# Module_main.net
KiCad netlist of a schematic drawn in Altium Designer
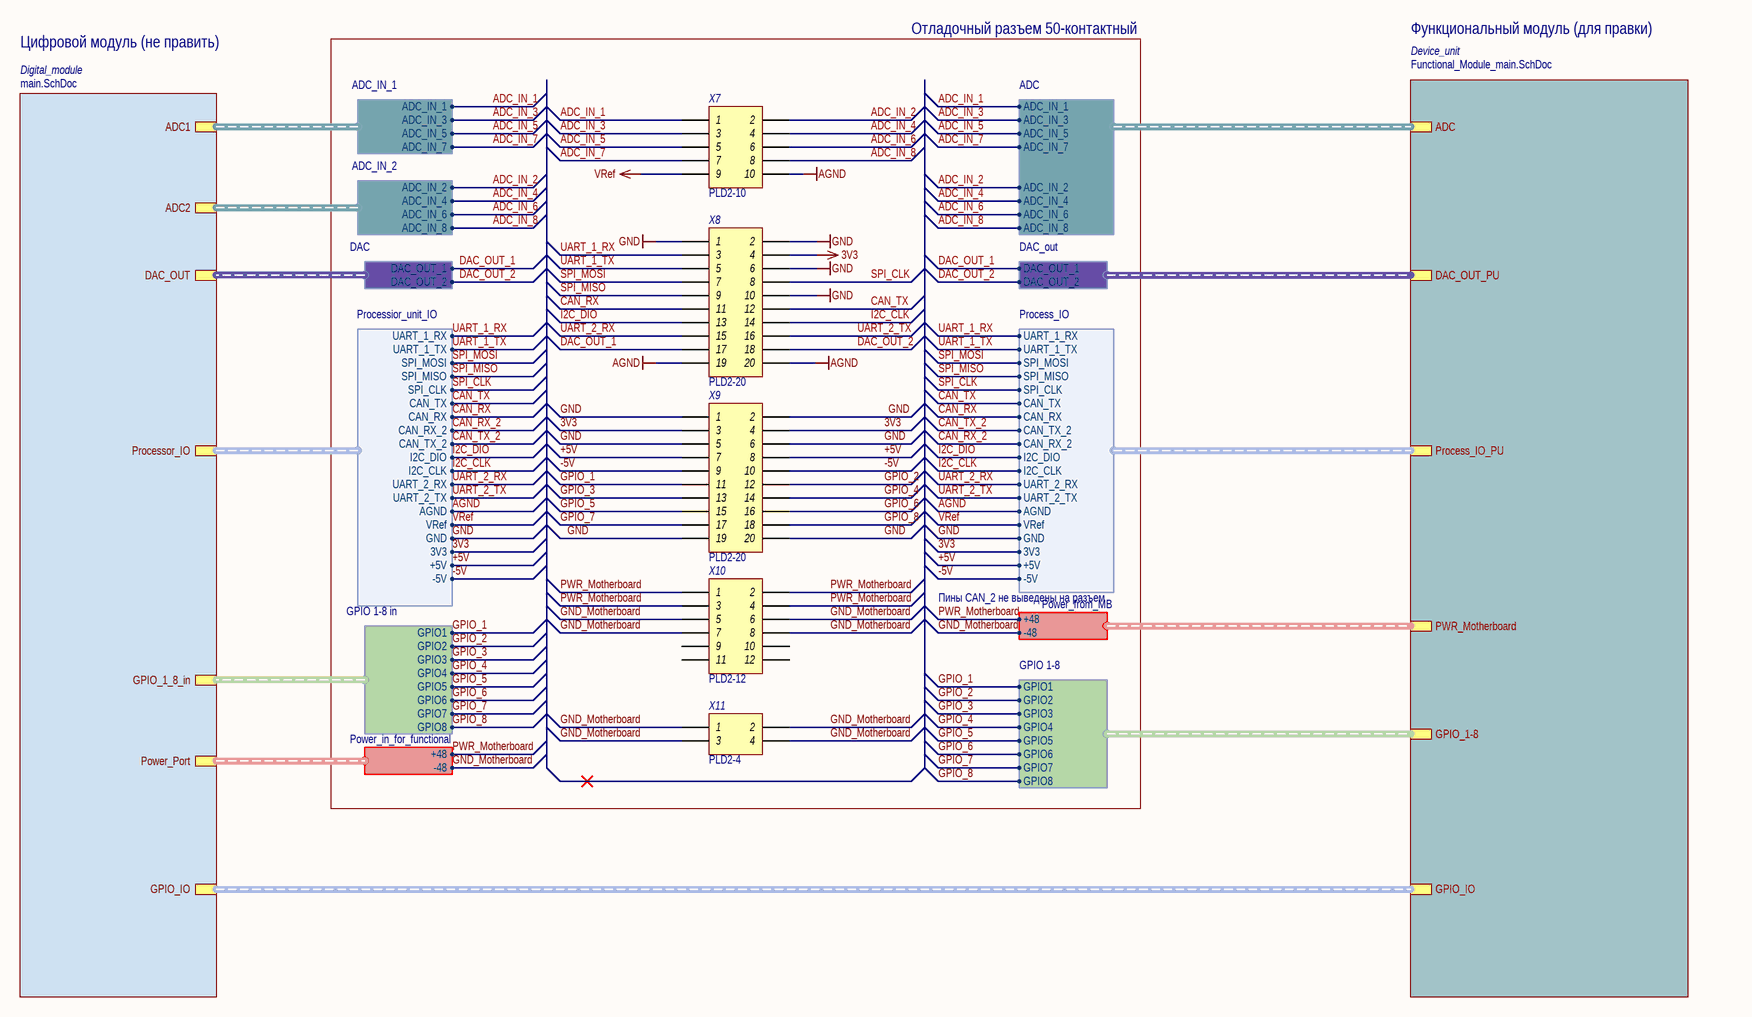
[diagram p0: Module_main.SchDoc]

(export (version "E")
  (design (tool "Eeschema 10.0.6"))
  (components
    (comp (ref "X7")
      (value "Header 2X10")
      (footprint "PBD2-10s")
      (description "Header, 10-Pin, Dual row")
      (fields (field (name "НАИМЕНОВАНИЕ") "PLD2-10"))
      (libsource (lib "Connector") (part "PLD2-10"))
    )
    (comp (ref "X8")
      (value "Header 2X10")
      (footprint "PBD2-20s")
      (description "Header, 12-Pin, Dual row")
      (fields (field (name "НАИМЕНОВАНИЕ") "PLD2-20"))
      (libsource (lib "Connector") (part "PLD2-20"))
    )
    (comp (ref "X9")
      (value "Header 2X10")
      (footprint "PBD2-20s")
      (description "Header, 12-Pin, Dual row")
      (fields (field (name "НАИМЕНОВАНИЕ") "PLD2-20"))
      (libsource (lib "Connector") (part "PLD2-20"))
    )
    (comp (ref "X10")
      (value "Header 2X6")
      (footprint "PLD2-12R 2.54")
      (description "Header, 12-Pin, Dual row")
      (fields (field (name "НАИМЕНОВАНИЕ") "PLD2-12"))
      (libsource (lib "Connector") (part "PLD2-12"))
    )
    (comp (ref "X11")
      (value "Header 2X4")
      (footprint "PLD2-4 R 2.54")
      (description "Header, 4-Pin, Dual row")
      (fields (field (name "НАИМЕНОВАНИЕ") "PLD2-4"))
      (libsource (lib "Connector") (part "PLD2-4"))
    )
  )
  (nets
    (net (code "11") (name "/+5V") (class "Default")
      (node (ref "X9") (pin "7") (pinfunction "7_7") (pintype "passive"))
      (node (ref "X9") (pin "8") (pinfunction "8_8") (pintype "passive"))
    )
    (net (code "12") (name "/-5V") (class "Default")
      (node (ref "X9") (pin "10") (pinfunction "10_10") (pintype "passive"))
      (node (ref "X9") (pin "9") (pinfunction "9_9") (pintype "passive"))
    )
    (net (code "13") (name "/ADC_IN_1") (class "Default")
      (node (ref "X7") (pin "1") (pinfunction "1_1") (pintype "passive"))
    )
    (net (code "14") (name "/ADC_IN_2") (class "Default")
      (node (ref "X7") (pin "2") (pinfunction "2_2") (pintype "passive"))
    )
    (net (code "15") (name "/ADC_IN_3") (class "Default")
      (node (ref "X7") (pin "3") (pinfunction "3_3") (pintype "passive"))
    )
    (net (code "16") (name "/ADC_IN_4") (class "Default")
      (node (ref "X7") (pin "4") (pinfunction "4_4") (pintype "passive"))
    )
    (net (code "17") (name "/ADC_IN_5") (class "Default")
      (node (ref "X7") (pin "5") (pinfunction "5_5") (pintype "passive"))
    )
    (net (code "18") (name "/ADC_IN_6") (class "Default")
      (node (ref "X7") (pin "6") (pinfunction "6_6") (pintype "passive"))
    )
    (net (code "19") (name "/ADC_IN_7") (class "Default")
      (node (ref "X7") (pin "7") (pinfunction "7_7") (pintype "passive"))
    )
    (net (code "20") (name "/ADC_IN_8") (class "Default")
      (node (ref "X7") (pin "8") (pinfunction "8_8") (pintype "passive"))
    )
    (net (code "21") (name "/CAN_RX") (class "Default")
      (node (ref "X8") (pin "11") (pinfunction "11_11") (pintype "passive"))
    )
    (net (code "23") (name "/CAN_TX") (class "Default")
      (node (ref "X8") (pin "12") (pinfunction "12_12") (pintype "passive"))
    )
    (net (code "25") (name "/DAC_OUT_1") (class "Default")
      (node (ref "X8") (pin "17") (pinfunction "17_17") (pintype "passive"))
    )
    (net (code "26") (name "/DAC_OUT_2") (class "Default")
      (node (ref "X8") (pin "18") (pinfunction "18_18") (pintype "passive"))
    )
    (net (code "27") (name "/GND_Motherboard") (class "Default")
      (node (ref "X10") (pin "5") (pinfunction "5_5") (pintype "passive"))
      (node (ref "X10") (pin "6") (pinfunction "6_6") (pintype "passive"))
      (node (ref "X10") (pin "7") (pinfunction "7_7") (pintype "passive"))
      (node (ref "X10") (pin "8") (pinfunction "8_8") (pintype "passive"))
      (node (ref "X11") (pin "1") (pinfunction "1_1") (pintype "passive"))
      (node (ref "X11") (pin "2") (pinfunction "2_2") (pintype "passive"))
      (node (ref "X11") (pin "3") (pinfunction "3_3") (pintype "passive"))
      (node (ref "X11") (pin "4") (pinfunction "4_4") (pintype "passive"))
    )
    (net (code "28") (name "/GPIO_1") (class "Default")
      (node (ref "X9") (pin "11") (pinfunction "11_11") (pintype "passive"))
    )
    (net (code "29") (name "/GPIO_2") (class "Default")
      (node (ref "X9") (pin "12") (pinfunction "12_12") (pintype "passive"))
    )
    (net (code "30") (name "/GPIO_3") (class "Default")
      (node (ref "X9") (pin "13") (pinfunction "13_13") (pintype "passive"))
    )
    (net (code "31") (name "/GPIO_4") (class "Default")
      (node (ref "X9") (pin "14") (pinfunction "14_14") (pintype "passive"))
    )
    (net (code "32") (name "/GPIO_5") (class "Default")
      (node (ref "X9") (pin "15") (pinfunction "15_15") (pintype "passive"))
    )
    (net (code "33") (name "/GPIO_6") (class "Default")
      (node (ref "X9") (pin "16") (pinfunction "16_16") (pintype "passive"))
    )
    (net (code "34") (name "/GPIO_7") (class "Default")
      (node (ref "X9") (pin "17") (pinfunction "17_17") (pintype "passive"))
    )
    (net (code "35") (name "/GPIO_8") (class "Default")
      (node (ref "X9") (pin "18") (pinfunction "18_18") (pintype "passive"))
    )
    (net (code "37") (name "/I2C_CLK") (class "Default")
      (node (ref "X8") (pin "14") (pinfunction "14_14") (pintype "passive"))
    )
    (net (code "38") (name "/I2C_DIO") (class "Default")
      (node (ref "X8") (pin "13") (pinfunction "13_13") (pintype "passive"))
    )
    (net (code "39") (name "/PWR_Motherboard") (class "Default")
      (node (ref "X10") (pin "1") (pinfunction "1_1") (pintype "passive"))
      (node (ref "X10") (pin "2") (pinfunction "2_2") (pintype "passive"))
      (node (ref "X10") (pin "3") (pinfunction "3_3") (pintype "passive"))
      (node (ref "X10") (pin "4") (pinfunction "4_4") (pintype "passive"))
    )
    (net (code "40") (name "/SPI_CLK") (class "Default")
      (node (ref "X8") (pin "8") (pinfunction "8_8") (pintype "passive"))
    )
    (net (code "41") (name "/SPI_MISO") (class "Default")
      (node (ref "X8") (pin "9") (pinfunction "9_9") (pintype "passive"))
    )
    (net (code "42") (name "/SPI_MOSI") (class "Default")
      (node (ref "X8") (pin "7") (pinfunction "7_7") (pintype "passive"))
    )
    (net (code "43") (name "/UART_1_RX") (class "Default")
      (node (ref "X8") (pin "3") (pinfunction "3_3") (pintype "passive"))
    )
    (net (code "44") (name "/UART_1_TX") (class "Default")
      (node (ref "X8") (pin "5") (pinfunction "5_5") (pintype "passive"))
    )
    (net (code "45") (name "/UART_2_RX") (class "Default")
      (node (ref "X8") (pin "15") (pinfunction "15_15") (pintype "passive"))
    )
    (net (code "46") (name "/UART_2_TX") (class "Default")
      (node (ref "X8") (pin "16") (pinfunction "16_16") (pintype "passive"))
    )
    (net (code "58") (name "3V3") (class "Default")
      (node (ref "X8") (pin "4") (pinfunction "4_4") (pintype "passive"))
      (node (ref "X9") (pin "3") (pinfunction "3_3") (pintype "passive"))
      (node (ref "X9") (pin "4") (pinfunction "4_4") (pintype "passive"))
    )
    (net (code "59") (name "AGND") (class "Default")
      (node (ref "X7") (pin "10") (pinfunction "10_10") (pintype "passive"))
      (node (ref "X8") (pin "19") (pinfunction "19_19") (pintype "passive"))
      (node (ref "X8") (pin "20") (pinfunction "20_20") (pintype "passive"))
    )
    (net (code "60") (name "GND") (class "Default")
      (node (ref "X8") (pin "1") (pinfunction "1_1") (pintype "passive"))
      (node (ref "X8") (pin "10") (pinfunction "10_10") (pintype "passive"))
      (node (ref "X8") (pin "2") (pinfunction "2_2") (pintype "passive"))
      (node (ref "X8") (pin "6") (pinfunction "6_6") (pintype "passive"))
      (node (ref "X9") (pin "1") (pinfunction "1_1") (pintype "passive"))
      (node (ref "X9") (pin "19") (pinfunction "19_19") (pintype "passive"))
      (node (ref "X9") (pin "2") (pinfunction "2_2") (pintype "passive"))
      (node (ref "X9") (pin "20") (pinfunction "20_20") (pintype "passive"))
      (node (ref "X9") (pin "5") (pinfunction "5_5") (pintype "passive"))
      (node (ref "X9") (pin "6") (pinfunction "6_6") (pintype "passive"))
    )
    (net (code "61") (name "VRef") (class "Default")
      (node (ref "X7") (pin "9") (pinfunction "9_9") (pintype "passive"))
    )
    (net (code "62") (name "unconnected-(X10-Pad9)") (class "Default")
      (node (ref "X10") (pin "9") (pinfunction "9_9") (pintype "passive"))
    )
    (net (code "63") (name "unconnected-(X10-Pad10)") (class "Default")
      (node (ref "X10") (pin "10") (pinfunction "10_10") (pintype "passive"))
    )
    (net (code "64") (name "unconnected-(X10-Pad11)") (class "Default")
      (node (ref "X10") (pin "11") (pinfunction "11_11") (pintype "passive"))
    )
    (net (code "65") (name "unconnected-(X10-Pad12)") (class "Default")
      (node (ref "X10") (pin "12") (pinfunction "12_12") (pintype "passive"))
    )
  )
)
